# P22_MIPI_DSI.net
KiCad netlist of a schematic drawn in Altium Designer
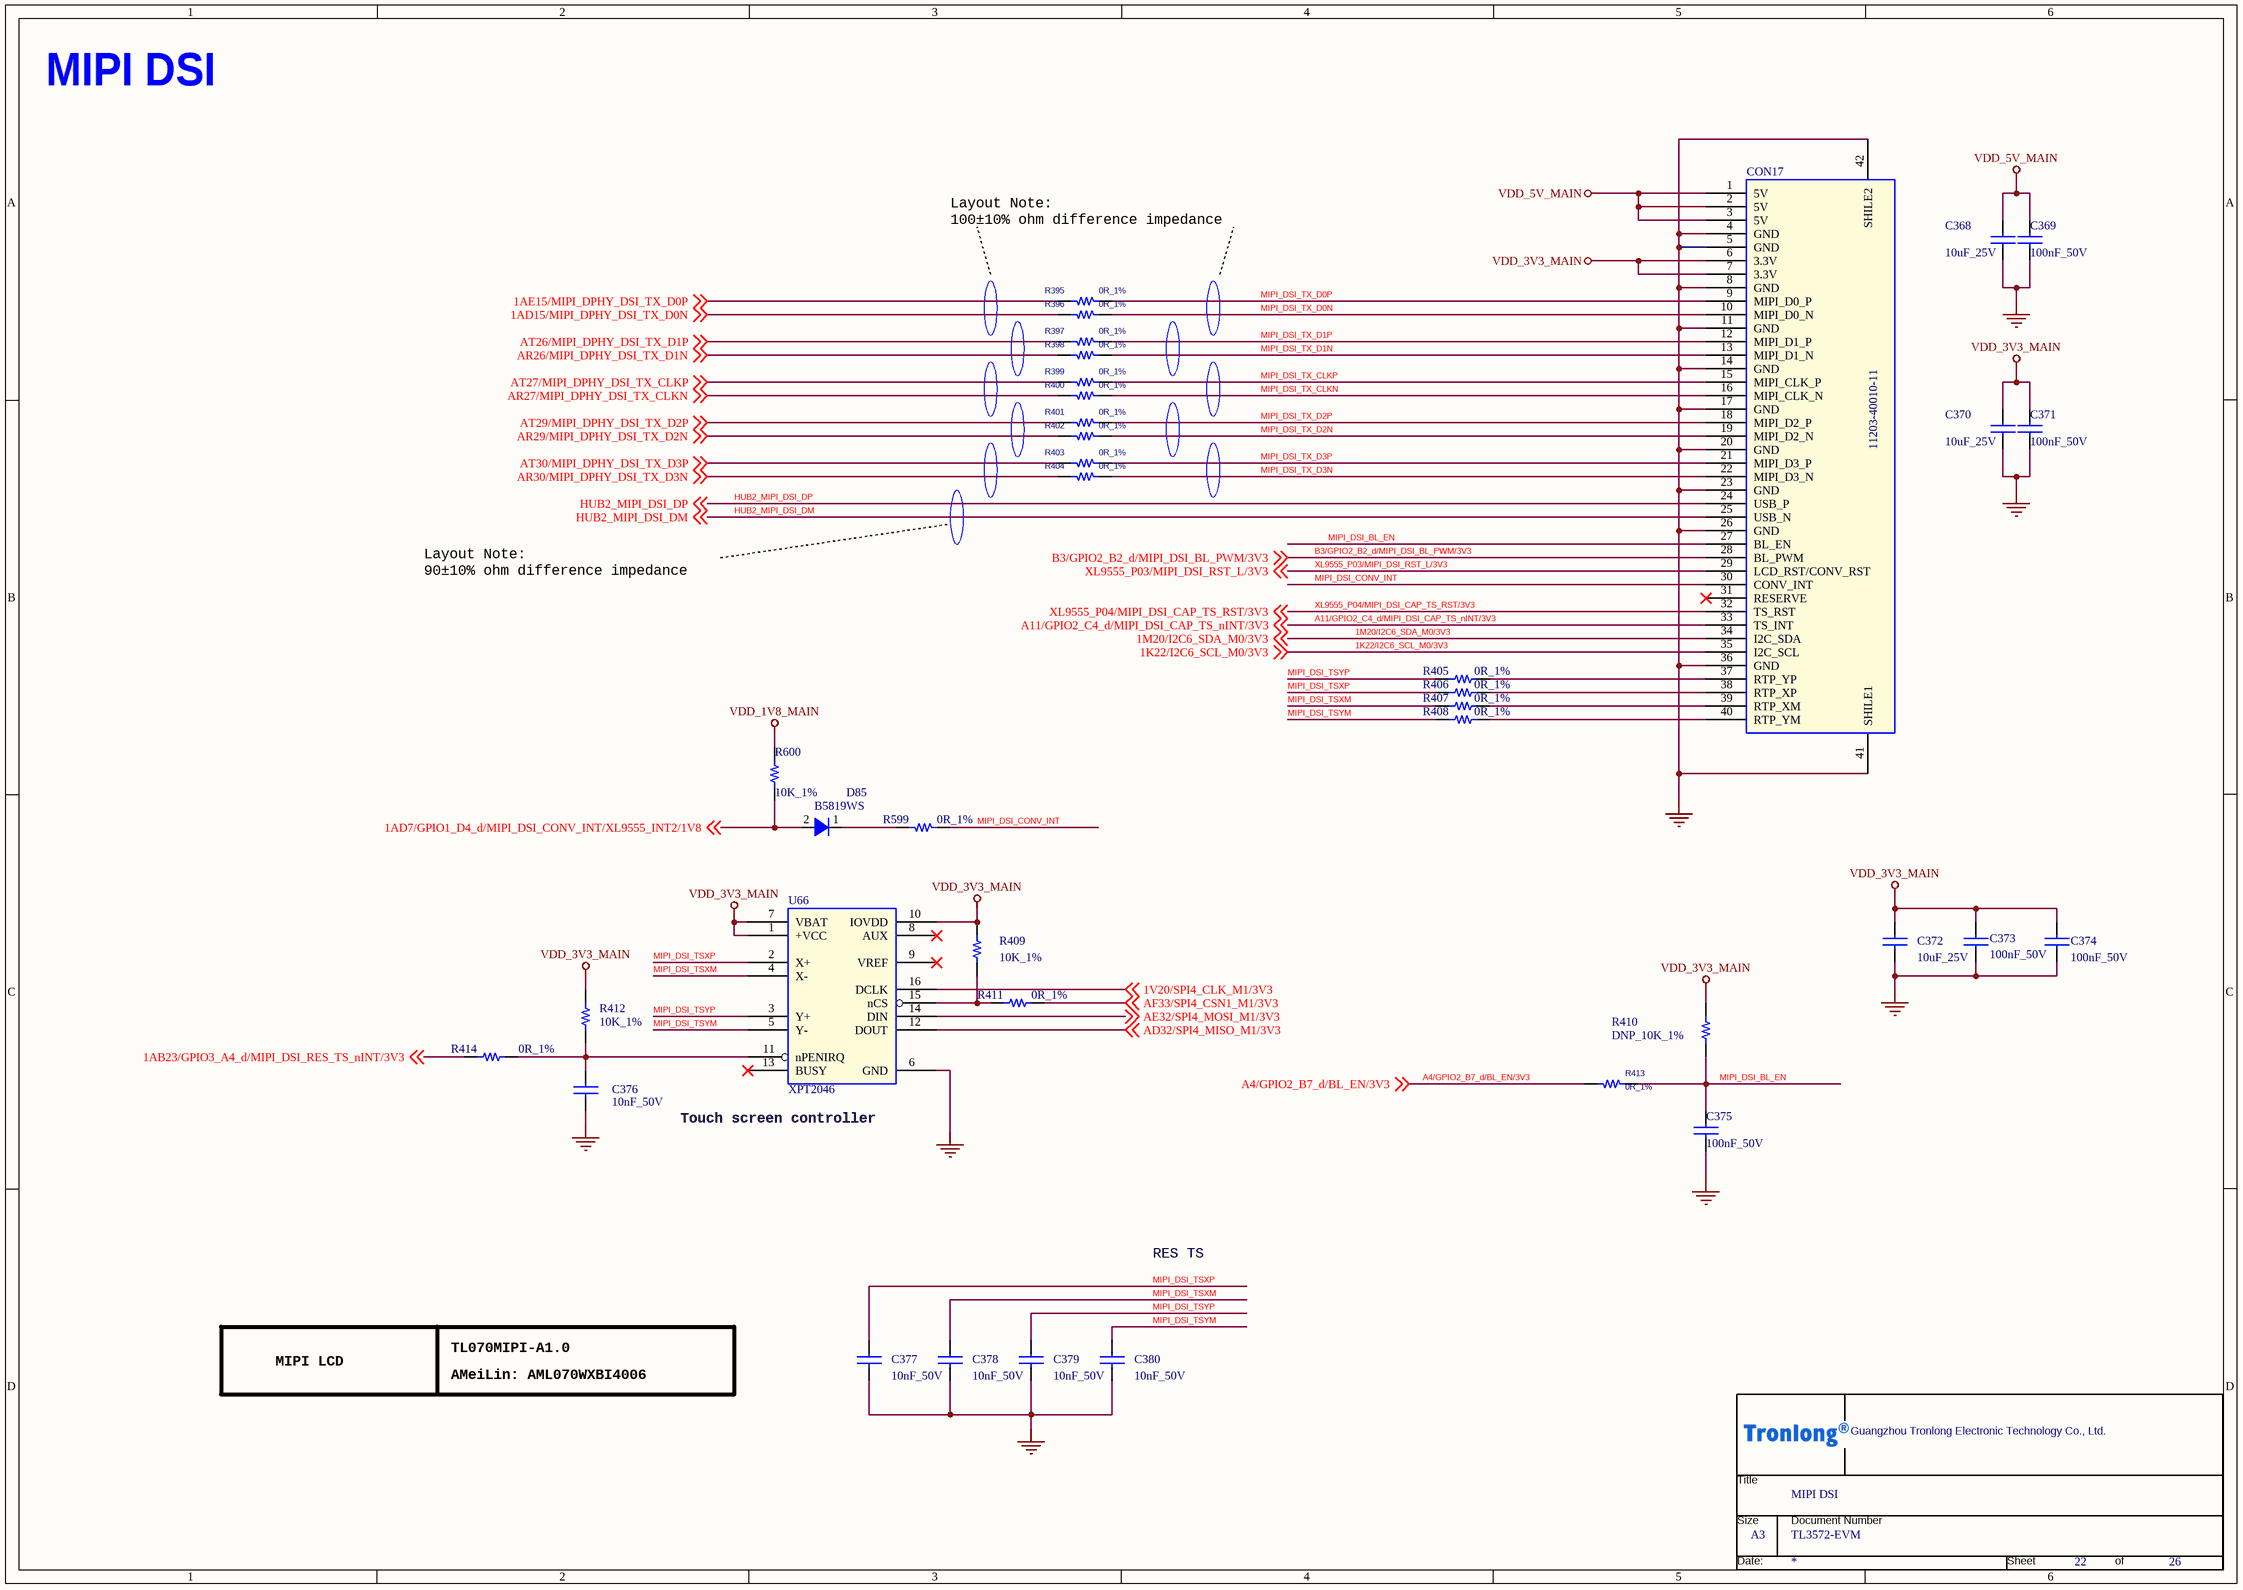
[diagram p0: P22_MIPI DSI.SchDoc]

(export (version "E")
  (design (tool "Eeschema 10.0.6"))
  (components
    (comp (ref "*")
      (value "Tronlong_TITTLE_20211115")
      (fields
        (field (name "DOC") "TL3572-EVM")
        (field (name "TITLE") "MIPI DSI")
        (field (name "ORGNAME") "Guangzhou Tronlong Electronic Technology Co., Ltd.")
        (field (name "PAGE SIZE") "A3")
        (field (name "PAGE NUMBER") "22")
        (field (name "PAGE COUNT") "26")
      )
      (libsource (lib "*") (part "Tronlong_TITTLE_20211115"))
    )
    (comp (ref "C368")
      (value "10uF_25V")
      (footprint "C0603")
      (description "贴片陶瓷电容,10uF,20%,25V,X5R")
      (fields
        (field (name "MANUFACTURER") "广东风华高新科技股份有限公司（FH）")
        (field (name "MANUFACTURER PARTNUMBER") "0603X106M250NT")
      )
      (libsource (lib "*") (part "CAP NP_Dup2"))
    )
    (comp (ref "C369")
      (value "100nF_50V")
      (footprint "C0402")
      (description "贴片陶瓷电容,100nF,10%,50V,X7R")
      (fields
        (field (name "MANUFACTURER") "广东风华高新科技股份有限公司（FH）")
        (field (name "MANUFACTURER PARTNUMBER") "0402B104K500NT")
      )
      (libsource (lib "*") (part "CAP NP_Dup2"))
    )
    (comp (ref "C370")
      (value "10uF_25V")
      (footprint "C0603")
      (description "贴片陶瓷电容,10uF,20%,25V,X5R")
      (fields
        (field (name "MANUFACTURER PARTNUMBER") "0603X106M250NT")
        (field (name "MANUFACTURER") "广东风华高新科技股份有限公司（FH）")
      )
      (libsource (lib "*") (part "CAP NP_Dup2"))
    )
    (comp (ref "C371")
      (value "100nF_50V")
      (footprint "C0402")
      (description "贴片陶瓷电容,100nF,10%,50V,X7R")
      (fields
        (field (name "MANUFACTURER") "广东风华高新科技股份有限公司（FH）")
        (field (name "MANUFACTURER PARTNUMBER") "0402B104K500NT")
      )
      (libsource (lib "*") (part "CAP NP_Dup2"))
    )
    (comp (ref "C372")
      (value "10uF_25V")
      (footprint "C0603")
      (description "贴片陶瓷电容,10uF,20%,25V,X5R")
      (fields
        (field (name "MANUFACTURER") "广东风华高新科技股份有限公司（FH）")
        (field (name "MANUFACTURER PARTNUMBER") "0603X106M250NT")
      )
      (libsource (lib "*") (part "CAP NP_Dup2"))
    )
    (comp (ref "C373")
      (value "100nF_50V")
      (footprint "C0402")
      (description "贴片陶瓷电容,100nF,10%,50V,X7R")
      (fields
        (field (name "MANUFACTURER PARTNUMBER") "0402B104K500NT")
        (field (name "MANUFACTURER") "广东风华高新科技股份有限公司（FH）")
      )
      (libsource (lib "*") (part "CAP NP_Dup2"))
    )
    (comp (ref "C374")
      (value "100nF_50V")
      (footprint "C0402")
      (description "贴片陶瓷电容,100nF,10%,50V,X7R")
      (fields
        (field (name "MANUFACTURER PARTNUMBER") "0402B104K500NT")
        (field (name "MANUFACTURER") "广东风华高新科技股份有限公司（FH）")
      )
      (libsource (lib "*") (part "CAP NP_Dup2"))
    )
    (comp (ref "C375")
      (value "100nF_50V")
      (footprint "C0402")
      (description "贴片陶瓷电容,100nF,10%,50V,X7R")
      (fields
        (field (name "MANUFACTURER") "广东风华高新科技股份有限公司（FH）")
        (field (name "MANUFACTURER PARTNUMBER") "0402B104K500NT")
      )
      (libsource (lib "*") (part "CAP NP_Dup2"))
    )
    (comp (ref "C376")
      (value "10nF_50V")
      (footprint "C0402")
      (description "贴片陶瓷电容,10nF,10%,50V,X7R")
      (fields
        (field (name "MANUFACTURER PARTNUMBER") "0402B103K500NT")
        (field (name "MANUFACTURER") "广东风华高新科技股份有限公司（FH）")
      )
      (libsource (lib "*") (part "CAP NP_Dup2"))
    )
    (comp (ref "C377")
      (value "10nF_50V")
      (footprint "C0402")
      (description "贴片陶瓷电容,10nF,10%,50V,X7R")
      (fields
        (field (name "MANUFACTURER") "广东风华高新科技股份有限公司（FH）")
        (field (name "MANUFACTURER PARTNUMBER") "0402B103K500NT")
      )
      (libsource (lib "*") (part "CAP NP_Dup2"))
    )
    (comp (ref "C378")
      (value "10nF_50V")
      (footprint "C0402")
      (description "贴片陶瓷电容,10nF,10%,50V,X7R")
      (fields
        (field (name "MANUFACTURER") "广东风华高新科技股份有限公司（FH）")
        (field (name "MANUFACTURER PARTNUMBER") "0402B103K500NT")
      )
      (libsource (lib "*") (part "CAP NP_Dup2"))
    )
    (comp (ref "C379")
      (value "10nF_50V")
      (footprint "C0402")
      (description "贴片陶瓷电容,10nF,10%,50V,X7R")
      (fields
        (field (name "MANUFACTURER") "广东风华高新科技股份有限公司（FH）")
        (field (name "MANUFACTURER PARTNUMBER") "0402B103K500NT")
      )
      (libsource (lib "*") (part "CAP NP_Dup2"))
    )
    (comp (ref "C380")
      (value "10nF_50V")
      (footprint "C0402")
      (description "贴片陶瓷电容,10nF,10%,50V,X7R")
      (fields
        (field (name "MANUFACTURER") "广东风华高新科技股份有限公司（FH）")
        (field (name "MANUFACTURER PARTNUMBER") "0402B103K500NT")
      )
      (libsource (lib "*") (part "CAP NP_Dup2"))
    )
    (comp (ref "CON17")
      (value "11203-40010-11")
      (footprint "CON_FFC_0D5_40P")
      (description "FFC座,40P,0.5mm间距,翻盖下接式,H=2.0mm")
      (fields (field (name "MANUFACTURER") "深圳市联畅精密电子有限公司(LCP)"))
      (libsource (lib "*") (part "40PIN FPC CON_5"))
    )
    (comp (ref "D85")
      (value "B5819WS")
      (footprint "SOD-323")
      (description "肖特基二极管,VR=40V,IF=1A,VF=0.6V@1A")
      (fields (field (name "MFR") "On Semiconductor") (field (name "TIINTPARTNUMBER") "1E0013"))
      (libsource (lib "*") (part "Diode200mA250V_2"))
    )
    (comp (ref "R395")
      (value "0R_1%")
      (footprint "R0402")
      (description "贴片电阻,0R,±1%,1/16W")
      (fields
        (field (name "MANUFACTURER PARTNUMBER") "RC-02000FT")
        (field (name "MANUFACTURER") "广东风华高新科技股份有限公司（FH）")
      )
      (libsource (lib "*") (part "Resistor_Dup3"))
    )
    (comp (ref "R396")
      (value "0R_1%")
      (footprint "R0402")
      (description "贴片电阻,0R,±1%,1/16W")
      (fields
        (field (name "MANUFACTURER PARTNUMBER") "RC-02000FT")
        (field (name "MANUFACTURER") "广东风华高新科技股份有限公司（FH）")
      )
      (libsource (lib "*") (part "Resistor_Dup3"))
    )
    (comp (ref "R397")
      (value "0R_1%")
      (footprint "R0402")
      (description "贴片电阻,0R,±1%,1/16W")
      (fields
        (field (name "MANUFACTURER") "广东风华高新科技股份有限公司（FH）")
        (field (name "MANUFACTURER PARTNUMBER") "RC-02000FT")
      )
      (libsource (lib "*") (part "Resistor_Dup3"))
    )
    (comp (ref "R398")
      (value "0R_1%")
      (footprint "R0402")
      (description "贴片电阻,0R,±1%,1/16W")
      (fields
        (field (name "MANUFACTURER") "广东风华高新科技股份有限公司（FH）")
        (field (name "MANUFACTURER PARTNUMBER") "RC-02000FT")
      )
      (libsource (lib "*") (part "Resistor_Dup3"))
    )
    (comp (ref "R399")
      (value "0R_1%")
      (footprint "R0402")
      (description "贴片电阻,0R,±1%,1/16W")
      (fields
        (field (name "MANUFACTURER") "广东风华高新科技股份有限公司（FH）")
        (field (name "MANUFACTURER PARTNUMBER") "RC-02000FT")
      )
      (libsource (lib "*") (part "Resistor_Dup3"))
    )
    (comp (ref "R400")
      (value "0R_1%")
      (footprint "R0402")
      (description "贴片电阻,0R,±1%,1/16W")
      (fields
        (field (name "MANUFACTURER PARTNUMBER") "RC-02000FT")
        (field (name "MANUFACTURER") "广东风华高新科技股份有限公司（FH）")
      )
      (libsource (lib "*") (part "Resistor_Dup3"))
    )
    (comp (ref "R401")
      (value "0R_1%")
      (footprint "R0402")
      (description "贴片电阻,0R,±1%,1/16W")
      (fields
        (field (name "MANUFACTURER") "广东风华高新科技股份有限公司（FH）")
        (field (name "MANUFACTURER PARTNUMBER") "RC-02000FT")
      )
      (libsource (lib "*") (part "Resistor_Dup3"))
    )
    (comp (ref "R402")
      (value "0R_1%")
      (footprint "R0402")
      (description "贴片电阻,0R,±1%,1/16W")
      (fields
        (field (name "MANUFACTURER") "广东风华高新科技股份有限公司（FH）")
        (field (name "MANUFACTURER PARTNUMBER") "RC-02000FT")
      )
      (libsource (lib "*") (part "Resistor_Dup3"))
    )
    (comp (ref "R403")
      (value "0R_1%")
      (footprint "R0402")
      (description "贴片电阻,0R,±1%,1/16W")
      (fields
        (field (name "MANUFACTURER") "广东风华高新科技股份有限公司（FH）")
        (field (name "MANUFACTURER PARTNUMBER") "RC-02000FT")
      )
      (libsource (lib "*") (part "Resistor_Dup3"))
    )
    (comp (ref "R404")
      (value "0R_1%")
      (footprint "R0402")
      (description "贴片电阻,0R,±1%,1/16W")
      (fields
        (field (name "MANUFACTURER") "广东风华高新科技股份有限公司（FH）")
        (field (name "MANUFACTURER PARTNUMBER") "RC-02000FT")
      )
      (libsource (lib "*") (part "Resistor_Dup3"))
    )
    (comp (ref "R405")
      (value "0R_1%")
      (footprint "R0402")
      (description "贴片电阻,0R,±1%,1/16W")
      (fields
        (field (name "MANUFACTURER") "广东风华高新科技股份有限公司（FH）")
        (field (name "MANUFACTURER PARTNUMBER") "RC-02000FT")
      )
      (libsource (lib "*") (part "Resistor_Dup3"))
    )
    (comp (ref "R406")
      (value "0R_1%")
      (footprint "R0402")
      (description "贴片电阻,0R,±1%,1/16W")
      (fields
        (field (name "MANUFACTURER PARTNUMBER") "RC-02000FT")
        (field (name "MANUFACTURER") "广东风华高新科技股份有限公司（FH）")
      )
      (libsource (lib "*") (part "Resistor_Dup3"))
    )
    (comp (ref "R407")
      (value "0R_1%")
      (footprint "R0402")
      (description "贴片电阻,0R,±1%,1/16W")
      (fields
        (field (name "MANUFACTURER") "广东风华高新科技股份有限公司（FH）")
        (field (name "MANUFACTURER PARTNUMBER") "RC-02000FT")
      )
      (libsource (lib "*") (part "Resistor_Dup3"))
    )
    (comp (ref "R408")
      (value "0R_1%")
      (footprint "R0402")
      (description "贴片电阻,0R,±1%,1/16W")
      (fields
        (field (name "MANUFACTURER PARTNUMBER") "RC-02000FT")
        (field (name "MANUFACTURER") "广东风华高新科技股份有限公司（FH）")
      )
      (libsource (lib "*") (part "Resistor_Dup3"))
    )
    (comp (ref "R409")
      (value "10K_1%")
      (footprint "R0402")
      (description "贴片电阻,10K,±1%,1/16W")
      (fields
        (field (name "MANUFACTURER") "广东风华高新科技股份有限公司（FH）")
        (field (name "MANUFACTURER PARTNUMBER") "RC-02K1002FT")
      )
      (libsource (lib "*") (part "Resistor_Dup3"))
    )
    (comp (ref "R410")
      (value "DNP_10K_1%")
      (footprint "R0402")
      (description "贴片电阻,10K,±1%,1/16W")
      (fields
        (field (name "MANUFACTURER PARTNUMBER") "RC-02K1002FT")
        (field (name "MANUFACTURER") "广东风华高新科技股份有限公司（FH）")
      )
      (libsource (lib "*") (part "Resistor_Dup3"))
    )
    (comp (ref "R411")
      (value "0R_1%")
      (footprint "R0402")
      (description "贴片电阻,0R,±1%,1/16W")
      (fields
        (field (name "MANUFACTURER PARTNUMBER") "RC-02000FT")
        (field (name "MANUFACTURER") "广东风华高新科技股份有限公司（FH）")
      )
      (libsource (lib "*") (part "Resistor_Dup3"))
    )
    (comp (ref "R412")
      (value "10K_1%")
      (footprint "R0402")
      (description "贴片电阻,10K,±1%,1/16W")
      (fields
        (field (name "MANUFACTURER PARTNUMBER") "RC-02K1002FT")
        (field (name "MANUFACTURER") "广东风华高新科技股份有限公司（FH）")
      )
      (libsource (lib "*") (part "Resistor_Dup3"))
    )
    (comp (ref "R413")
      (value "0R_1%")
      (footprint "R0402")
      (description "贴片电阻,0R,±1%,1/16W")
      (fields
        (field (name "MANUFACTURER PARTNUMBER") "RC-02000FT")
        (field (name "MANUFACTURER") "广东风华高新科技股份有限公司（FH）")
      )
      (libsource (lib "*") (part "Resistor_Dup3"))
    )
    (comp (ref "R414")
      (value "0R_1%")
      (footprint "R0402")
      (description "贴片电阻,0R,±1%,1/16W")
      (fields
        (field (name "MANUFACTURER") "广东风华高新科技股份有限公司（FH）")
        (field (name "MANUFACTURER PARTNUMBER") "RC-02000FT")
      )
      (libsource (lib "*") (part "Resistor_Dup3"))
    )
    (comp (ref "R599")
      (value "0R_1%")
      (footprint "R0402")
      (description "贴片电阻,0R,±1%,1/16W")
      (fields
        (field (name "MANUFACTURER") "广东风华高新科技股份有限公司（FH）")
        (field (name "MANUFACTURER PARTNUMBER") "RC-02000FT")
      )
      (libsource (lib "*") (part "Resistor"))
    )
    (comp (ref "R600")
      (value "10K_1%")
      (footprint "R0402")
      (description "贴片电阻,10K,±1%,1/16W")
      (fields
        (field (name "MANUFACTURER") "广东风华高新科技股份有限公司（FH）")
        (field (name "MANUFACTURER PARTNUMBER") "RC-02K1002FT")
      )
      (libsource (lib "*") (part "Resistor"))
    )
    (comp (ref "U66")
      (value "XPT2046")
      (footprint "TSSOP16")
      (description "触摸屏控制器")
      (fields (field (name "MANUFACTURER") "深圳市矽普特科技有限公司（XPT）"))
      (libsource (lib "*") (part "TSC2046IPW"))
    )
  )
  (nets
    (net (code "1") (name "/MIPI_DSI_BL_EN") (class "Default")
      (node (ref "C375") (pin "1") (pinfunction "1_1") (pintype "passive"))
      (node (ref "CON17") (pin "27") (pinfunction "BL_EN_27") (pintype "passive"))
      (node (ref "R410") (pin "2") (pinfunction "2_2") (pintype "passive"))
      (node (ref "R413") (pin "2") (pinfunction "2_2") (pintype "passive"))
    )
    (net (code "2") (name "/MIPI_DSI_CONV_INT") (class "Default")
      (node (ref "CON17") (pin "30") (pinfunction "CONV_INT_30") (pintype "passive"))
      (node (ref "R599") (pin "2") (pinfunction "2_2") (pintype "passive"))
    )
    (net (code "3") (name "/MIPI_DSI_TSXM") (class "Default")
      (node (ref "C378") (pin "1") (pinfunction "1_1") (pintype "passive"))
      (node (ref "R407") (pin "2") (pinfunction "2_2") (pintype "passive"))
      (node (ref "U66") (pin "4") (pinfunction "X-_4") (pintype "passive"))
    )
    (net (code "4") (name "/MIPI_DSI_TSXP") (class "Default")
      (node (ref "C377") (pin "1") (pinfunction "1_1") (pintype "passive"))
      (node (ref "R406") (pin "2") (pinfunction "2_2") (pintype "passive"))
      (node (ref "U66") (pin "2") (pinfunction "X+_2") (pintype "passive"))
    )
    (net (code "5") (name "/MIPI_DSI_TSYM") (class "Default")
      (node (ref "C380") (pin "1") (pinfunction "1_1") (pintype "passive"))
      (node (ref "R408") (pin "2") (pinfunction "2_2") (pintype "passive"))
      (node (ref "U66") (pin "5") (pinfunction "Y-_5") (pintype "passive"))
    )
    (net (code "6") (name "/MIPI_DSI_TSYP") (class "Default")
      (node (ref "C379") (pin "1") (pinfunction "1_1") (pintype "passive"))
      (node (ref "R405") (pin "2") (pinfunction "2_2") (pintype "passive"))
      (node (ref "U66") (pin "3") (pinfunction "Y+_3") (pintype "passive"))
    )
    (net (code "7") (name "/MIPI_DSI_TX_CLKN") (class "Default")
      (node (ref "CON17") (pin "16") (pinfunction "MIPI_CLK_N_16") (pintype "passive"))
      (node (ref "R400") (pin "2") (pinfunction "2_2") (pintype "passive"))
    )
    (net (code "8") (name "/MIPI_DSI_TX_CLKP") (class "Default")
      (node (ref "CON17") (pin "15") (pinfunction "MIPI_CLK_P_15") (pintype "passive"))
      (node (ref "R399") (pin "2") (pinfunction "2_2") (pintype "passive"))
    )
    (net (code "9") (name "/MIPI_DSI_TX_D0N") (class "Default")
      (node (ref "CON17") (pin "10") (pinfunction "MIPI_D0_N_10") (pintype "passive"))
      (node (ref "R396") (pin "2") (pinfunction "2_2") (pintype "passive"))
    )
    (net (code "10") (name "/MIPI_DSI_TX_D0P") (class "Default")
      (node (ref "CON17") (pin "9") (pinfunction "MIPI_D0_P_9") (pintype "passive"))
      (node (ref "R395") (pin "2") (pinfunction "2_2") (pintype "passive"))
    )
    (net (code "11") (name "/MIPI_DSI_TX_D1N") (class "Default")
      (node (ref "CON17") (pin "13") (pinfunction "MIPI_D1_N_13") (pintype "passive"))
      (node (ref "R398") (pin "2") (pinfunction "2_2") (pintype "passive"))
    )
    (net (code "12") (name "/MIPI_DSI_TX_D1P") (class "Default")
      (node (ref "CON17") (pin "12") (pinfunction "MIPI_D1_P_12") (pintype "passive"))
      (node (ref "R397") (pin "2") (pinfunction "2_2") (pintype "passive"))
    )
    (net (code "13") (name "/MIPI_DSI_TX_D2N") (class "Default")
      (node (ref "CON17") (pin "19") (pinfunction "MIPI_D2_N_19") (pintype "passive"))
      (node (ref "R402") (pin "2") (pinfunction "2_2") (pintype "passive"))
    )
    (net (code "14") (name "/MIPI_DSI_TX_D2P") (class "Default")
      (node (ref "CON17") (pin "18") (pinfunction "MIPI_D2_P_18") (pintype "passive"))
      (node (ref "R401") (pin "2") (pinfunction "2_2") (pintype "passive"))
    )
    (net (code "15") (name "/MIPI_DSI_TX_D3N") (class "Default")
      (node (ref "CON17") (pin "22") (pinfunction "MIPI_D3_N_22") (pintype "passive"))
      (node (ref "R404") (pin "2") (pinfunction "2_2") (pintype "passive"))
    )
    (net (code "16") (name "/MIPI_DSI_TX_D3P") (class "Default")
      (node (ref "CON17") (pin "21") (pinfunction "MIPI_D3_P_21") (pintype "passive"))
      (node (ref "R403") (pin "2") (pinfunction "2_2") (pintype "passive"))
    )
    (net (code "17") (name "1AB23{slash}GPIO3_A4_d{slash}MIPI_DSI_RES_TS_nINT{slash}3V3") (class "Default")
      (node (ref "R414") (pin "1") (pinfunction "1_1") (pintype "passive"))
    )
    (net (code "18") (name "1AD7{slash}GPIO1_D4_d{slash}MIPI_DSI_CONV_INT{slash}XL9555_INT2{slash}1V8") (class "Default")
      (node (ref "D85") (pin "2") (pinfunction "Cathode_2") (pintype "passive"))
      (node (ref "R600") (pin "2") (pinfunction "2_2") (pintype "passive"))
    )
    (net (code "19") (name "1AD15{slash}MIPI_DPHY_DSI_TX_D0N") (class "Default")
      (node (ref "R396") (pin "1") (pinfunction "1_1") (pintype "passive"))
    )
    (net (code "20") (name "1AE15{slash}MIPI_DPHY_DSI_TX_D0P") (class "Default")
      (node (ref "R395") (pin "1") (pinfunction "1_1") (pintype "passive"))
    )
    (net (code "21") (name "1K22{slash}I2C6_SCL_M0{slash}3V3") (class "Default")
      (node (ref "CON17") (pin "35") (pinfunction "I2C_SCL_35") (pintype "passive"))
    )
    (net (code "22") (name "1M20{slash}I2C6_SDA_M0{slash}3V3") (class "Default")
      (node (ref "CON17") (pin "34") (pinfunction "I2C_SDA_34") (pintype "passive"))
    )
    (net (code "23") (name "1V20{slash}SPI4_CLK_M1{slash}3V3") (class "Default")
      (node (ref "U66") (pin "16") (pinfunction "DCLK_16") (pintype "passive"))
    )
    (net (code "24") (name "A4{slash}GPIO2_B7_d{slash}BL_EN{slash}3V3") (class "Default")
      (node (ref "R413") (pin "1") (pinfunction "1_1") (pintype "passive"))
    )
    (net (code "25") (name "A11{slash}GPIO2_C4_d{slash}MIPI_DSI_CAP_TS_nINT{slash}3V3") (class "Default")
      (node (ref "CON17") (pin "33") (pinfunction "TS_INT_33") (pintype "passive"))
    )
    (net (code "26") (name "AD32{slash}SPI4_MISO_M1{slash}3V3") (class "Default")
      (node (ref "U66") (pin "12") (pinfunction "DOUT_12") (pintype "passive"))
    )
    (net (code "27") (name "AE32{slash}SPI4_MOSI_M1{slash}3V3") (class "Default")
      (node (ref "U66") (pin "14") (pinfunction "DIN_14") (pintype "passive"))
    )
    (net (code "28") (name "AF33{slash}SPI4_CSN1_M1{slash}3V3") (class "Default")
      (node (ref "R411") (pin "2") (pinfunction "2_2") (pintype "passive"))
    )
    (net (code "29") (name "AR26{slash}MIPI_DPHY_DSI_TX_D1N") (class "Default")
      (node (ref "R398") (pin "1") (pinfunction "1_1") (pintype "passive"))
    )
    (net (code "30") (name "AR27{slash}MIPI_DPHY_DSI_TX_CLKN") (class "Default")
      (node (ref "R400") (pin "1") (pinfunction "1_1") (pintype "passive"))
    )
    (net (code "31") (name "AR29{slash}MIPI_DPHY_DSI_TX_D2N") (class "Default")
      (node (ref "R402") (pin "1") (pinfunction "1_1") (pintype "passive"))
    )
    (net (code "32") (name "AR30{slash}MIPI_DPHY_DSI_TX_D3N") (class "Default")
      (node (ref "R404") (pin "1") (pinfunction "1_1") (pintype "passive"))
    )
    (net (code "33") (name "AT26{slash}MIPI_DPHY_DSI_TX_D1P") (class "Default")
      (node (ref "R397") (pin "1") (pinfunction "1_1") (pintype "passive"))
    )
    (net (code "34") (name "AT27{slash}MIPI_DPHY_DSI_TX_CLKP") (class "Default")
      (node (ref "R399") (pin "1") (pinfunction "1_1") (pintype "passive"))
    )
    (net (code "35") (name "AT29{slash}MIPI_DPHY_DSI_TX_D2P") (class "Default")
      (node (ref "R401") (pin "1") (pinfunction "1_1") (pintype "passive"))
    )
    (net (code "36") (name "AT30{slash}MIPI_DPHY_DSI_TX_D3P") (class "Default")
      (node (ref "R403") (pin "1") (pinfunction "1_1") (pintype "passive"))
    )
    (net (code "37") (name "B3{slash}GPIO2_B2_d{slash}MIPI_DSI_BL_PWM{slash}3V3") (class "Default")
      (node (ref "CON17") (pin "28") (pinfunction "BL_PWM_28") (pintype "passive"))
    )
    (net (code "38") (name "GND") (class "Default")
      (node (ref "C368") (pin "2") (pinfunction "2_2") (pintype "passive"))
      (node (ref "C369") (pin "2") (pinfunction "2_2") (pintype "passive"))
      (node (ref "C370") (pin "2") (pinfunction "2_2") (pintype "passive"))
      (node (ref "C371") (pin "2") (pinfunction "2_2") (pintype "passive"))
      (node (ref "C372") (pin "2") (pinfunction "2_2") (pintype "passive"))
      (node (ref "C373") (pin "2") (pinfunction "2_2") (pintype "passive"))
      (node (ref "C374") (pin "2") (pinfunction "2_2") (pintype "passive"))
      (node (ref "C375") (pin "2") (pinfunction "2_2") (pintype "passive"))
      (node (ref "C376") (pin "2") (pinfunction "2_2") (pintype "passive"))
      (node (ref "C377") (pin "2") (pinfunction "2_2") (pintype "passive"))
      (node (ref "C378") (pin "2") (pinfunction "2_2") (pintype "passive"))
      (node (ref "C379") (pin "2") (pinfunction "2_2") (pintype "passive"))
      (node (ref "C380") (pin "2") (pinfunction "2_2") (pintype "passive"))
      (node (ref "CON17") (pin "11") (pinfunction "GND_11") (pintype "power_in"))
      (node (ref "CON17") (pin "14") (pinfunction "GND_14") (pintype "power_in"))
      (node (ref "CON17") (pin "17") (pinfunction "GND_17") (pintype "power_in"))
      (node (ref "CON17") (pin "20") (pinfunction "GND_20") (pintype "power_in"))
      (node (ref "CON17") (pin "23") (pinfunction "GND_23") (pintype "power_in"))
      (node (ref "CON17") (pin "26") (pinfunction "GND_26") (pintype "power_in"))
      (node (ref "CON17") (pin "36") (pinfunction "GND_36") (pintype "power_in"))
      (node (ref "CON17") (pin "4") (pinfunction "GND_4") (pintype "power_in"))
      (node (ref "CON17") (pin "41") (pinfunction "SHILE1_41") (pintype "passive"))
      (node (ref "CON17") (pin "42") (pinfunction "SHILE2_42") (pintype "passive"))
      (node (ref "CON17") (pin "5") (pinfunction "GND_5") (pintype "power_in"))
      (node (ref "CON17") (pin "8") (pinfunction "GND_8") (pintype "power_in"))
      (node (ref "U66") (pin "6") (pinfunction "GND_6") (pintype "passive"))
    )
    (net (code "39") (name "HUB2_MIPI_DSI_DM") (class "Default")
      (node (ref "CON17") (pin "25") (pinfunction "USB_N_25") (pintype "passive"))
    )
    (net (code "40") (name "HUB2_MIPI_DSI_DP") (class "Default")
      (node (ref "CON17") (pin "24") (pinfunction "USB_P_24") (pintype "passive"))
    )
    (net (code "41") (name "Net-(CON17-RTP_XM)") (class "Default")
      (node (ref "CON17") (pin "39") (pinfunction "RTP_XM_39") (pintype "passive"))
      (node (ref "R407") (pin "1") (pinfunction "1_1") (pintype "passive"))
    )
    (net (code "42") (name "Net-(CON17-RTP_XP)") (class "Default")
      (node (ref "CON17") (pin "38") (pinfunction "RTP_XP_38") (pintype "passive"))
      (node (ref "R406") (pin "1") (pinfunction "1_1") (pintype "passive"))
    )
    (net (code "43") (name "Net-(CON17-RTP_YM)") (class "Default")
      (node (ref "CON17") (pin "40") (pinfunction "RTP_YM_40") (pintype "passive"))
      (node (ref "R408") (pin "1") (pinfunction "1_1") (pintype "passive"))
    )
    (net (code "44") (name "Net-(CON17-RTP_YP)") (class "Default")
      (node (ref "CON17") (pin "37") (pinfunction "RTP_YP_37") (pintype "passive"))
      (node (ref "R405") (pin "1") (pinfunction "1_1") (pintype "passive"))
    )
    (net (code "45") (name "Net-(D85-Anode)") (class "Default")
      (node (ref "D85") (pin "1") (pinfunction "Anode_1") (pintype "passive"))
      (node (ref "R599") (pin "1") (pinfunction "1_1") (pintype "passive"))
    )
    (net (code "46") (name "Net-(U66-nCS)") (class "Default")
      (node (ref "R409") (pin "2") (pinfunction "2_2") (pintype "passive"))
      (node (ref "R411") (pin "1") (pinfunction "1_1") (pintype "passive"))
      (node (ref "U66") (pin "15") (pinfunction "nCS_15") (pintype "passive"))
    )
    (net (code "47") (name "Net-(U66-nPENIRQ)") (class "Default")
      (node (ref "C376") (pin "1") (pinfunction "1_1") (pintype "passive"))
      (node (ref "R412") (pin "2") (pinfunction "2_2") (pintype "passive"))
      (node (ref "R414") (pin "2") (pinfunction "2_2") (pintype "passive"))
      (node (ref "U66") (pin "11") (pinfunction "nPENIRQ_11") (pintype "passive"))
    )
    (net (code "48") (name "VDD_1V8_MAIN") (class "Default")
      (node (ref "R600") (pin "1") (pinfunction "1_1") (pintype "passive"))
    )
    (net (code "49") (name "VDD_3V3_MAIN") (class "Default")
      (node (ref "C370") (pin "1") (pinfunction "1_1") (pintype "passive"))
      (node (ref "C371") (pin "1") (pinfunction "1_1") (pintype "passive"))
      (node (ref "C372") (pin "1") (pinfunction "1_1") (pintype "passive"))
      (node (ref "C373") (pin "1") (pinfunction "1_1") (pintype "passive"))
      (node (ref "C374") (pin "1") (pinfunction "1_1") (pintype "passive"))
      (node (ref "CON17") (pin "6") (pinfunction "3.3V_6") (pintype "power_in"))
      (node (ref "CON17") (pin "7") (pinfunction "3.3V_7") (pintype "power_in"))
      (node (ref "R409") (pin "1") (pinfunction "1_1") (pintype "passive"))
      (node (ref "R410") (pin "1") (pinfunction "1_1") (pintype "passive"))
      (node (ref "R412") (pin "1") (pinfunction "1_1") (pintype "passive"))
      (node (ref "U66") (pin "1") (pinfunction "+VCC_1") (pintype "passive"))
      (node (ref "U66") (pin "10") (pinfunction "IOVDD_10") (pintype "passive"))
      (node (ref "U66") (pin "7") (pinfunction "VBAT_7") (pintype "passive"))
    )
    (net (code "50") (name "VDD_5V_MAIN") (class "Default")
      (node (ref "C368") (pin "1") (pinfunction "1_1") (pintype "passive"))
      (node (ref "C369") (pin "1") (pinfunction "1_1") (pintype "passive"))
      (node (ref "CON17") (pin "1") (pinfunction "5V_1") (pintype "power_in"))
      (node (ref "CON17") (pin "2") (pinfunction "5V_2") (pintype "power_in"))
      (node (ref "CON17") (pin "3") (pinfunction "5V_3") (pintype "power_in"))
    )
    (net (code "51") (name "XL9555_P03{slash}MIPI_DSI_RST_L{slash}3V3") (class "Default")
      (node (ref "CON17") (pin "29") (pinfunction "LCD_RST/CONV_RST_29") (pintype "passive"))
    )
    (net (code "52") (name "XL9555_P04{slash}MIPI_DSI_CAP_TS_RST{slash}3V3") (class "Default")
      (node (ref "CON17") (pin "32") (pinfunction "TS_RST_32") (pintype "passive"))
    )
    (net (code "53") (name "unconnected-(CON17-RESERVE-Pad31)") (class "Default")
      (node (ref "CON17") (pin "31") (pinfunction "RESERVE_31") (pintype "passive+no_connect"))
    )
    (net (code "54") (name "unconnected-(U66-AUX-Pad8)") (class "Default")
      (node (ref "U66") (pin "8") (pinfunction "AUX_8") (pintype "passive+no_connect"))
    )
    (net (code "55") (name "unconnected-(U66-BUSY-Pad13)") (class "Default")
      (node (ref "U66") (pin "13") (pinfunction "BUSY_13") (pintype "passive+no_connect"))
    )
    (net (code "56") (name "unconnected-(U66-VREF-Pad9)") (class "Default")
      (node (ref "U66") (pin "9") (pinfunction "VREF_9") (pintype "passive+no_connect"))
    )
  )
)
